# 01-MSP430.net
KiCad netlist of a schematic drawn in Altium Designer
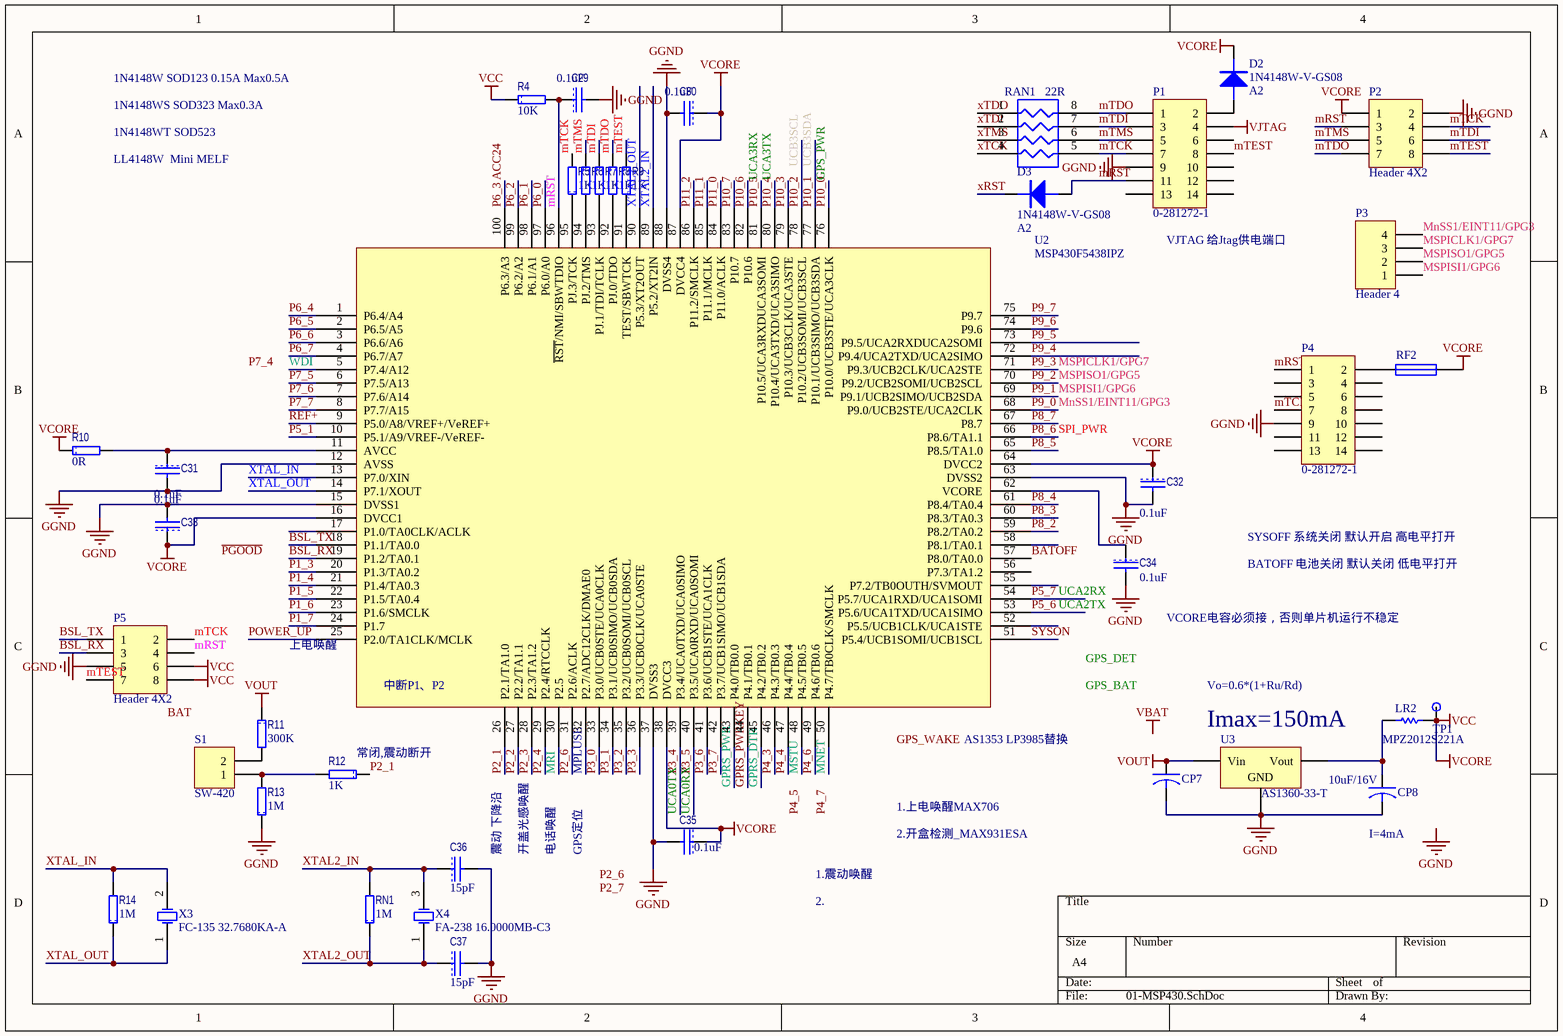
[diagram p0: 01-MSP430.SchDoc]

(export (version "E")
  (design (tool "Eeschema 10.0.6"))
  (components
    (comp (ref "C29")
      (value "0.1uF")
      (footprint "1608[0603]C")
      (description "多层陶瓷电容器MLCC - SMD/SMT 0603 0.1uF 50volts X7R 10%")
      (fields (field (name "MANUFACTURER") "TDK") (field (name "MANUFACTURER PART NUMBER") "C1608X7R1H104K"))
      (libsource (lib "*") (part "CAP"))
    )
    (comp (ref "C30")
      (value "0.1uF")
      (footprint "1608[0603]C")
      (description "多层陶瓷电容器MLCC - SMD/SMT 0603 0.1uF 50volts X7R 10%")
      (fields (field (name "MANUFACTURER") "TDK") (field (name "MANUFACTURER PART NUMBER") "C1608X7R1H104K"))
      (libsource (lib "*") (part "CAP"))
    )
    (comp (ref "C31")
      (value "0.1uF")
      (footprint "1608[0603]C")
      (description "多层陶瓷电容器MLCC - SMD/SMT 0603 0.1uF 50volts X7R 10%")
      (fields (field (name "MANUFACTURER") "TDK") (field (name "MANUFACTURER PART NUMBER") "C1608X7R1H104K"))
      (libsource (lib "*") (part "CAP"))
    )
    (comp (ref "C32")
      (value "0.1uF")
      (footprint "1608[0603]C")
      (description "多层陶瓷电容器MLCC - SMD/SMT 0603 0.1uF 50volts X7R 10%")
      (fields (field (name "MANUFACTURER") "TDK") (field (name "MANUFACTURER PART NUMBER") "C1608X7R1H104K"))
      (libsource (lib "*") (part "CAP"))
    )
    (comp (ref "C33")
      (value "0.1uF")
      (footprint "1608[0603]C")
      (description "多层陶瓷电容器MLCC - SMD/SMT 0603 0.1uF 50volts X7R 10%")
      (fields (field (name "MANUFACTURER") "TDK") (field (name "MANUFACTURER PART NUMBER") "C1608X7R1H104K"))
      (libsource (lib "*") (part "CAP"))
    )
    (comp (ref "C34")
      (value "0.1uF")
      (footprint "1608[0603]C")
      (description "多层陶瓷电容器MLCC - SMD/SMT 0603 0.1uF 50volts X7R 10%")
      (fields (field (name "MANUFACTURER") "TDK") (field (name "MANUFACTURER PART NUMBER") "C1608X7R1H104K"))
      (libsource (lib "*") (part "CAP"))
    )
    (comp (ref "C35")
      (value "0.1uF")
      (footprint "1608[0603]C")
      (description "多层陶瓷电容器MLCC - SMD/SMT 0603 0.1uF 50volts X7R 10%")
      (fields (field (name "MANUFACTURER") "TDK") (field (name "MANUFACTURER PART NUMBER") "C1608X7R1H104K"))
      (libsource (lib "*") (part "CAP"))
    )
    (comp (ref "C36")
      (value "15pF")
      (footprint "1608[0603]")
      (description "多层陶瓷电容器MLCC - SMD/SMT 0603 15pF 50volts C0G 5%")
      (fields (field (name "MANUFACTURER") "TDK") (field (name "MANUFACTURER PART NUMBER") "C1608C0G1H150J"))
      (libsource (lib "*") (part "CAP"))
    )
    (comp (ref "C37")
      (value "15pF")
      (footprint "1608[0603]")
      (description "多层陶瓷电容器MLCC - SMD/SMT 0603 15pF 50volts C0G 5%")
      (fields (field (name "MANUFACTURER") "TDK") (field (name "MANUFACTURER PART NUMBER") "C1608C0G1H150J"))
      (libsource (lib "*") (part "CAP"))
    )
    (comp (ref "CP7")
      (value "TAJA106K016RNJ")
      (footprint "3216[1206]CB")
      (description "钽质电容器-固体SMD 16volts 10uF 10%")
      (fields (field (name "MANUFACTURER") "AVX"))
      (libsource (lib "*") (part "CAPACITOR"))
    )
    (comp (ref "CP8")
      (value "10uF/16V")
      (footprint "3216[1206]CB")
      (description "钽质电容器-固体SMD 16volts 10uF 10%")
      (fields (field (name "MANUFACTURER") "AVX") (field (name "MANUFACTURER PART NUMBER") "TAJA106K016RNJ"))
      (libsource (lib "*") (part "CAPACITOR"))
    )
    (comp (ref "D2")
      (value "1N4148W-V-GS08")
      (footprint "SOD123")
      (description "二极管 - 通用，功率，开关 100V Io/150mA")
      (fields (field (name "MANUFACTURER") "Vishay Semiconductors") (field (name "ALTIUM_VALUE") "A2"))
      (libsource (lib "IN4148") (part "1N4148W"))
    )
    (comp (ref "D3")
      (value "1N4148W-V-GS08")
      (footprint "SOD123")
      (description "二极管 - 通用，功率，开关 100V Io/150mA")
      (fields (field (name "MANUFACTURER") "Vishay Semiconductors") (field (name "ALTIUM_VALUE") "A2"))
      (libsource (lib "IN4148") (part "1N4148W"))
    )
    (comp (ref "LR2")
      (value "MPZ2012S221A")
      (footprint "2012[0805]")
      (description "电磁干扰滤波珠子、扼流圈和阵列 Ferrite Chip Beads")
      (fields (field (name "MANUFACTURER") "TDK"))
      (libsource (lib "Miscellaneous Devices") (part "Res Semi"))
    )
    (comp (ref "P1")
      (value "0-281272-1")
      (footprint "HDR2X7")
      (description "TE CONNECTIVITY 2.54mm / AMP - 0-281272-1 - HEADER STRAIGHT 14WAY")
      (fields (field (name "MANUFACTURER") "TE CONNECTIVITY / AMP"))
      (libsource (lib "Miscellaneous Connectors") (part "Header 7X2"))
    )
    (comp (ref "P2")
      (value "Header 4X2")
      (footprint "HDR2X4")
      (description "插针 Header, 4-Pin, Dual row")
      (fields (field (name "PUBLISHER") "Altium Limited"))
      (libsource (lib "Miscellaneous Connectors") (part "Header 4X2"))
    )
    (comp (ref "P3")
      (value "Header 4")
      (footprint "HDR1X4")
      (description "插针 Header, 4-Pin")
      (fields (field (name "PUBLISHER") "Altium Limited"))
      (libsource (lib "Miscellaneous Connectors") (part "Header 4"))
    )
    (comp (ref "P4")
      (value "0-281272-1")
      (footprint "HDR2X7")
      (description "TE CONNECTIVITY 2.54mm / AMP - 0-281272-1 - HEADER STRAIGHT 14WAY")
      (fields (field (name "MANUFACTURER") "TE CONNECTIVITY / AMP"))
      (libsource (lib "Miscellaneous Connectors") (part "Header 7X2"))
    )
    (comp (ref "P5")
      (value "Header 4X2")
      (footprint "HDR2X4")
      (description "插针 Header, 4-Pin, Dual row")
      (fields (field (name "PUBLISHER") "Altium Limited"))
      (libsource (lib "Miscellaneous Connectors") (part "Header 4X2"))
    )
    (comp (ref "R4")
      (value "10K")
      (footprint "1608[0603]R")
      (description "厚膜电阻器 - SMD 1/10watt 10Kohms 1%")
      (fields
        (field (name "MANUFACTURER") "Vishay / Dale")
        (field (name "MANUFACTURER PART NUMBER") "CRCW060310K0FKEA")
      )
      (libsource (lib "10K 1%") (part "RES"))
    )
    (comp (ref "R5")
      (value "1K")
      (footprint "1608[0603]R")
      (description "厚膜电阻器 - SMD 1/10watt 1.0Kohms 1%")
      (fields
        (field (name "MANUFACTURER") "Vishay / Dale")
        (field (name "MANUFACTURER PART NUMBER") "CRCW06031K00FKEA")
      )
      (libsource (lib "1K 1%") (part "RES"))
    )
    (comp (ref "R6")
      (value "1K")
      (footprint "1608[0603]R")
      (description "厚膜电阻器 - SMD 1/10watt 1.0Kohms 1%")
      (fields
        (field (name "MANUFACTURER") "Vishay / Dale")
        (field (name "MANUFACTURER PART NUMBER") "CRCW06031K00FKEA")
      )
      (libsource (lib "1K 1%") (part "RES"))
    )
    (comp (ref "R7")
      (value "1K")
      (footprint "1608[0603]R")
      (description "厚膜电阻器 - SMD 1/10watt 1.0Kohms 1%")
      (fields
        (field (name "MANUFACTURER") "Vishay / Dale")
        (field (name "MANUFACTURER PART NUMBER") "CRCW06031K00FKEA")
      )
      (libsource (lib "1K 1%") (part "RES"))
    )
    (comp (ref "R8")
      (value "1K")
      (footprint "1608[0603]R")
      (description "厚膜电阻器 - SMD 1/10watt 1.0Kohms 1%")
      (fields
        (field (name "MANUFACTURER") "Vishay / Dale")
        (field (name "MANUFACTURER PART NUMBER") "CRCW06031K00FKEA")
      )
      (libsource (lib "1K 1%") (part "RES"))
    )
    (comp (ref "R9")
      (value "1K")
      (footprint "1608[0603]R")
      (description "厚膜电阻器 - SMD 1/10watt 1.0Kohms 1%")
      (fields
        (field (name "MANUFACTURER") "Vishay / Dale")
        (field (name "MANUFACTURER PART NUMBER") "CRCW06031K00FKEA")
      )
      (libsource (lib "1K 1%") (part "RES"))
    )
    (comp (ref "R10")
      (value "0R")
      (footprint "1608[0603]R")
      (description "厚膜电阻器 - SMD 1/10watt ZEROohm Jumper")
      (fields
        (field (name "MANUFACTURER") "Vishay / Dale")
        (field (name "MANUFACTURER PART NUMBER") "CRCW06030000ZSTA")
      )
      (libsource (lib "0R 1%") (part "RES"))
    )
    (comp (ref "R11")
      (value "300K")
      (footprint "1608[0603]R")
      (description "厚膜电阻器 - SMD 1/10watt 300Kohms 1%")
      (fields
        (field (name "MANUFACTURER") "Vishay / Dale")
        (field (name "MANUFACTURER PART NUMBER") "CRCW0603100KFKEA")
      )
      (libsource (lib "100K 1%") (part "RES"))
    )
    (comp (ref "R12")
      (value "1K")
      (footprint "1608[0603]R")
      (description "厚膜电阻器 - SMD 1/10watt 1.0Kohms 1%")
      (fields
        (field (name "MANUFACTURER") "Vishay / Dale")
        (field (name "MANUFACTURER PART NUMBER") "CRCW06031K00FKEA")
      )
      (libsource (lib "1K 1%") (part "RES"))
    )
    (comp (ref "R13")
      (value "1M")
      (footprint "1608[0603]R")
      (description "厚膜电阻器 - SMD 1/10watt 1.0Mohms 1%")
      (fields
        (field (name "MANUFACTURER") "Vishay / Dale")
        (field (name "MANUFACTURER PART NUMBER") "CRCW06031M00FKEA")
      )
      (libsource (lib "1M 1%") (part "RES"))
    )
    (comp (ref "R14")
      (value "1M")
      (footprint "1608[0603]R")
      (description "厚膜电阻器 - SMD 1/10watt 1.0Mohms 1%")
      (fields
        (field (name "MANUFACTURER") "Vishay / Dale")
        (field (name "MANUFACTURER PART NUMBER") "CRCW06031M00FKEA")
      )
      (libsource (lib "1M 1%") (part "RES"))
    )
    (comp (ref "RAN1")
      (value "22R")
      (footprint "R-AR4")
      (description "电阻器网络与阵列 8Term 22ohms 5% Convex")
      (fields
        (field (name "MANUFACTURER") "Vishay / Dale")
        (field (name "MANUFACTURER PART NUMBER") "CRA06S08322R0JTA")
      )
      (libsource (lib "*") (part "RP4R"))
    )
    (comp (ref "RF2")
      (value "0805L050WR")
      (footprint "2012[0805]F")
      (description "可复位保险丝 PTC 30V POLY SURF MOUNT 0805 .500A")
      (fields (field (name "MANUFACTURER") "Littelfuse"))
      (libsource (lib "*") (part "FUSE1"))
    )
    (comp (ref "RN1")
      (value "1M")
      (footprint "1608[0603]RN")
      (description "厚膜电阻器 - SMD 1/10watt 1.0Mohms 1%")
      (fields
        (field (name "MANUFACTURER") "Vishay / Dale")
        (field (name "MANUFACTURER PART NUMBER") "CRCW06031M00FKEA")
      )
      (libsource (lib "1M 1%") (part "RES"))
    )
    (comp (ref "S1")
      (value "SW-420")
      (footprint "SW-420")
      (description "插针 工业级震动传感器")
      (fields (field (name "PUBLISHER") "Altium Limited"))
      (libsource (lib "Miscellaneous Connectors") (part "Header 2"))
    )
    (comp (ref "TP1")
      (value "TP")
      (footprint "TP")
      (description "Test Point")
      (libsource (lib "S3C2440V9") (part "Test Point"))
    )
    (comp (ref "U2")
      (value "MSP430F5438IPZ")
      (footprint "TQFP100_N")
      (description "IC MCU 16BIT 256K FLASH 100-LQFP")
      (fields
        (field (name "MANUFACTURER") "Texas Instruments")
        (field (name "MANUFACTURER PART NUMBER") "MSP430F5438IPZR")
      )
      (libsource (lib "MSP430") (part "MSP430F5438"))
    )
    (comp (ref "U3")
      (value "AS1360-33-T")
      (footprint "SOT23_N")
      (description "LDO Voltage Controllers")
      (fields (field (name "MANUFACTURER") "ams"))
      (libsource (lib "Miscellaneous Devices") (part "Volt Reg"))
    )
    (comp (ref "X3")
      (value "FC-135 32.7680KA-A")
      (footprint "FC-135")
      (description "晶体 32.768KHz 20ppm 12.5pF -40C -85C")
      (fields (field (name "MANUFACTURER") "Epson Toyocom"))
      (libsource (lib "Miscellaneous Devices") (part "XTAL"))
    )
    (comp (ref "X4")
      (value "FA-238 16.0000MB-C3")
      (footprint "FA-238")
      (description "CRYSTAL 16MHZ 18PF SMD")
      (fields (field (name "MANUFACTURER") "EPSON"))
      (libsource (lib "") (part "XTAL_1"))
    )
  )
  (nets
    (net (code "1") (name "/ACC24") (class "Default")
      (node (ref "U2") (pin "100") (pinfunction "P6.3/A3_100") (pintype "passive"))
    )
    (net (code "3") (name "/BATOFF") (class "Default")
      (node (ref "U2") (pin "57") (pinfunction "P8.0/TA0.0_57") (pintype "passive"))
    )
    (net (code "4") (name "/BSL_RX") (class "Default")
      (node (ref "P5") (pin "3") (pinfunction "3_3") (pintype "passive"))
      (node (ref "U2") (pin "19") (pinfunction "P1.2/TA0.1_19") (pintype "passive"))
    )
    (net (code "5") (name "/BSL_TX") (class "Default")
      (node (ref "P5") (pin "1") (pinfunction "1_1") (pintype "passive"))
      (node (ref "U2") (pin "18") (pinfunction "P1.1/TA0.0_18") (pintype "passive"))
    )
    (net (code "6") (name "/GPRS_DTR") (class "Default")
      (node (ref "U2") (pin "45") (pinfunction "P4.2/TB0.2_45") (pintype "passive"))
    )
    (net (code "7") (name "/GPRS_PWR") (class "Default")
      (node (ref "U2") (pin "43") (pinfunction "P4.0/TB0.0_43") (pintype "passive"))
    )
    (net (code "8") (name "/GPRS_PWRKEY") (class "Default")
      (node (ref "U2") (pin "44") (pinfunction "P4.1/TB0.1_44") (pintype "passive"))
    )
    (net (code "11") (name "/GPS_PWR") (class "Default")
      (node (ref "U2") (pin "76") (pinfunction "P10.0/UCB3STE/UCA3CLK_76") (pintype "passive"))
    )
    (net (code "13") (name "/MNET") (class "Default")
      (node (ref "U2") (pin "50") (pinfunction "P4.7/TB0CLK/SMCLK_50") (pintype "passive"))
    )
    (net (code "14") (name "/MPLUSE") (class "Default")
      (node (ref "U2") (pin "32") (pinfunction "P2.7/ADC12CLK/DMAE0_32") (pintype "passive"))
    )
    (net (code "15") (name "/MRI") (class "Default")
      (node (ref "U2") (pin "30") (pinfunction "P2.5_30") (pintype "passive"))
    )
    (net (code "16") (name "/MSPICLK1{slash}GPG7") (class "Default")
      (node (ref "P3") (pin "3") (pinfunction "3_3") (pintype "passive"))
      (node (ref "U2") (pin "71") (pinfunction "P9.3/UCB2CLK/UCA2STE_71") (pintype "passive"))
    )
    (net (code "17") (name "/MSPISI1{slash}GPG6") (class "Default")
      (node (ref "P3") (pin "1") (pinfunction "1_1") (pintype "passive"))
      (node (ref "U2") (pin "69") (pinfunction "P9.1/UCB2SIMO/UCB2SDA_69") (pintype "passive"))
    )
    (net (code "18") (name "/MSPISO1{slash}GPG5") (class "Default")
      (node (ref "P3") (pin "2") (pinfunction "2_2") (pintype "passive"))
      (node (ref "U2") (pin "70") (pinfunction "P9.2/UCB2SOMI/UCB2SCL_70") (pintype "passive"))
    )
    (net (code "19") (name "/MSTU") (class "Default")
      (node (ref "U2") (pin "48") (pinfunction "P4.5/TB0.5_48") (pintype "passive"))
    )
    (net (code "20") (name "/MnSS1{slash}EINT11{slash}GPG3") (class "Default")
      (node (ref "P3") (pin "4") (pinfunction "4_4") (pintype "passive"))
      (node (ref "U2") (pin "68") (pinfunction "P9.0/UCB2STE/UCA2CLK_68") (pintype "passive"))
    )
    (net (code "21") (name "/P1_3") (class "Default")
      (node (ref "U2") (pin "20") (pinfunction "P1.3/TA0.2_20") (pintype "passive"))
    )
    (net (code "22") (name "/P1_4") (class "Default")
      (node (ref "U2") (pin "21") (pinfunction "P1.4/TA0.3_21") (pintype "passive"))
    )
    (net (code "23") (name "/P1_5") (class "Default")
      (node (ref "U2") (pin "22") (pinfunction "P1.5/TA0.4_22") (pintype "passive"))
    )
    (net (code "24") (name "/P1_6") (class "Default")
      (node (ref "U2") (pin "23") (pinfunction "P1.6/SMCLK_23") (pintype "passive"))
    )
    (net (code "25") (name "/P1_7") (class "Default")
      (node (ref "U2") (pin "24") (pinfunction "P1.7_24") (pintype "passive"))
    )
    (net (code "26") (name "/P2_1") (class "Default")
      (node (ref "R12") (pin "1") (pinfunction "1_1") (pintype "passive"))
      (node (ref "U2") (pin "26") (pinfunction "P2.1/TA1.0_26") (pintype "passive"))
    )
    (net (code "27") (name "/P2_2") (class "Default")
      (node (ref "U2") (pin "27") (pinfunction "P2.2/TA1.1_27") (pintype "passive"))
    )
    (net (code "28") (name "/P2_3") (class "Default")
      (node (ref "U2") (pin "28") (pinfunction "P2.3/TA1.2_28") (pintype "passive"))
    )
    (net (code "29") (name "/P2_4") (class "Default")
      (node (ref "U2") (pin "29") (pinfunction "P2.4/RTCCLK_29") (pintype "passive"))
    )
    (net (code "30") (name "/P2_6") (class "Default")
      (node (ref "U2") (pin "31") (pinfunction "P2.6/ACLK_31") (pintype "passive"))
    )
    (net (code "32") (name "/P3_0") (class "Default")
      (node (ref "U2") (pin "33") (pinfunction "P3.0/UCB0STE/UCA0CLK_33") (pintype "passive"))
    )
    (net (code "33") (name "/P3_1") (class "Default")
      (node (ref "U2") (pin "34") (pinfunction "P3.1/UCB0SIMO/UCB0SDA_34") (pintype "passive"))
    )
    (net (code "34") (name "/P3_2") (class "Default")
      (node (ref "U2") (pin "35") (pinfunction "P3.2/UCB0SOMI/UCB0SCL_35") (pintype "passive"))
    )
    (net (code "35") (name "/P3_3") (class "Default")
      (node (ref "U2") (pin "36") (pinfunction "P3.3/UCB0CLK/UCA0STE_36") (pintype "passive"))
    )
    (net (code "36") (name "/P3_4") (class "Default")
      (node (ref "U2") (pin "39") (pinfunction "P3.4/UCA0TXD/UCA0SIMO_39") (pintype "passive"))
    )
    (net (code "37") (name "/P3_5") (class "Default")
      (node (ref "U2") (pin "40") (pinfunction "P3.5/UCA0RXD/UCA0SOMI_40") (pintype "passive"))
    )
    (net (code "38") (name "/P3_6") (class "Default")
      (node (ref "U2") (pin "41") (pinfunction "P3.6/UCB1STE/UCA1CLK_41") (pintype "passive"))
    )
    (net (code "39") (name "/P3_7") (class "Default")
      (node (ref "U2") (pin "42") (pinfunction "P3.7/UCB1SIMO/UCB1SDA_42") (pintype "passive"))
    )
    (net (code "40") (name "/P4_3") (class "Default")
      (node (ref "U2") (pin "46") (pinfunction "P4.3/TB0.3_46") (pintype "passive"))
    )
    (net (code "41") (name "/P4_4") (class "Default")
      (node (ref "U2") (pin "47") (pinfunction "P4.4/TB0.4_47") (pintype "passive"))
    )
    (net (code "43") (name "/P4_6") (class "Default")
      (node (ref "U2") (pin "49") (pinfunction "P4.6/TB0.6_49") (pintype "passive"))
    )
    (net (code "45") (name "/P5_1") (class "Default")
      (node (ref "U2") (pin "10") (pinfunction "P5.1/A9/VREF-/VeREF-_10") (pintype "passive"))
    )
    (net (code "46") (name "/P5_6") (class "Default")
      (node (ref "U2") (pin "53") (pinfunction "P5.6/UCA1TXD/UCA1SIMO_53") (pintype "passive"))
    )
    (net (code "47") (name "/P5_7") (class "Default")
      (node (ref "U2") (pin "54") (pinfunction "P5.7/UCA1RXD/UCA1SOMI_54") (pintype "passive"))
    )
    (net (code "48") (name "/P6_0") (class "Default")
      (node (ref "U2") (pin "97") (pinfunction "P6.0/A0_97") (pintype "passive"))
    )
    (net (code "49") (name "/P6_1") (class "Default")
      (node (ref "U2") (pin "98") (pinfunction "P6.1/A1_98") (pintype "passive"))
    )
    (net (code "50") (name "/P6_2") (class "Default")
      (node (ref "U2") (pin "99") (pinfunction "P6.2/A2_99") (pintype "passive"))
    )
    (net (code "51") (name "/P6_4") (class "Default")
      (node (ref "U2") (pin "1") (pinfunction "P6.4/A4_1") (pintype "passive"))
    )
    (net (code "52") (name "/P6_5") (class "Default")
      (node (ref "U2") (pin "2") (pinfunction "P6.5/A5_2") (pintype "passive"))
    )
    (net (code "53") (name "/P6_6") (class "Default")
      (node (ref "U2") (pin "3") (pinfunction "P6.6/A6_3") (pintype "passive"))
    )
    (net (code "54") (name "/P6_7") (class "Default")
      (node (ref "U2") (pin "4") (pinfunction "P6.7/A7_4") (pintype "passive"))
    )
    (net (code "56") (name "/P7_5") (class "Default")
      (node (ref "U2") (pin "6") (pinfunction "P7.5/A13_6") (pintype "passive"))
    )
    (net (code "57") (name "/P7_6") (class "Default")
      (node (ref "U2") (pin "7") (pinfunction "P7.6/A14_7") (pintype "passive"))
    )
    (net (code "58") (name "/P7_7") (class "Default")
      (node (ref "U2") (pin "8") (pinfunction "P7.7/A15_8") (pintype "passive"))
    )
    (net (code "59") (name "/P8_2") (class "Default")
      (node (ref "U2") (pin "59") (pinfunction "P8.2/TA0.2_59") (pintype "passive"))
    )
    (net (code "60") (name "/P8_3") (class "Default")
      (node (ref "U2") (pin "60") (pinfunction "P8.3/TA0.3_60") (pintype "passive"))
    )
    (net (code "61") (name "/P8_4") (class "Default")
      (node (ref "U2") (pin "61") (pinfunction "P8.4/TA0.4_61") (pintype "passive"))
    )
    (net (code "62") (name "/P8_5") (class "Default")
      (node (ref "U2") (pin "65") (pinfunction "P8.5/TA1.0_65") (pintype "passive"))
    )
    (net (code "63") (name "/P8_6") (class "Default")
      (node (ref "U2") (pin "66") (pinfunction "P8.6/TA1.1_66") (pintype "passive"))
    )
    (net (code "64") (name "/P8_7") (class "Default")
      (node (ref "U2") (pin "67") (pinfunction "P8.7_67") (pintype "passive"))
    )
    (net (code "65") (name "/P9_4") (class "Default")
      (node (ref "U2") (pin "72") (pinfunction "P9.4/UCA2TXD/UCA2SIMO_72") (pintype "passive"))
    )
    (net (code "66") (name "/P9_5") (class "Default")
      (node (ref "U2") (pin "73") (pinfunction "P9.5/UCA2RXDUCA2SOMI_73") (pintype "passive"))
    )
    (net (code "67") (name "/P9_6") (class "Default")
      (node (ref "U2") (pin "74") (pinfunction "P9.6_74") (pintype "passive"))
    )
    (net (code "68") (name "/P9_7") (class "Default")
      (node (ref "U2") (pin "75") (pinfunction "P9.7_75") (pintype "passive"))
    )
    (net (code "69") (name "/P10_1") (class "Default")
      (node (ref "U2") (pin "77") (pinfunction "P10.1/UCB3SIMO/UCB3SDA_77") (pintype "passive"))
    )
    (net (code "70") (name "/P10_2") (class "Default")
      (node (ref "U2") (pin "78") (pinfunction "P10.2/UCB3SOMI/UCB3SCL_78") (pintype "passive"))
    )
    (net (code "71") (name "/P10_3") (class "Default")
      (node (ref "U2") (pin "79") (pinfunction "P10.3/UCB3CLK/UCA3STE_79") (pintype "passive"))
    )
    (net (code "72") (name "/P10_4") (class "Default")
      (node (ref "U2") (pin "80") (pinfunction "P10.4/UCA3TXD/UCA3SIMO_80") (pintype "passive"))
    )
    (net (code "73") (name "/P10_5") (class "Default")
      (node (ref "U2") (pin "81") (pinfunction "P10.5/UCA3RXDUCA3SOMI_81") (pintype "passive"))
    )
    (net (code "74") (name "/P10_6") (class "Default")
      (node (ref "U2") (pin "82") (pinfunction "P10.6_82") (pintype "passive"))
    )
    (net (code "75") (name "/P10_7") (class "Default")
      (node (ref "U2") (pin "83") (pinfunction "P10.7_83") (pintype "passive"))
    )
    (net (code "76") (name "/P11_0") (class "Default")
      (node (ref "U2") (pin "84") (pinfunction "P11.0/ACLK_84") (pintype "passive"))
    )
    (net (code "77") (name "/P11_1") (class "Default")
      (node (ref "U2") (pin "85") (pinfunction "P11.1/MCLK_85") (pintype "passive"))
    )
    (net (code "78") (name "/P11_2") (class "Default")
      (node (ref "U2") (pin "86") (pinfunction "P11.2/SMCLK_86") (pintype "passive"))
    )
    (net (code "79") (name "/POWER_UP") (class "Default")
      (node (ref "U2") (pin "25") (pinfunction "P2.0/TA1CLK/MCLK_25") (pintype "passive"))
    )
    (net (code "80") (name "/REF+") (class "Default")
      (node (ref "U2") (pin "9") (pinfunction "P5.0/A8/VREF+/VeREF+_9") (pintype "passive"))
    )
    (net (code "81") (name "/SYSON") (class "Default")
      (node (ref "U2") (pin "51") (pinfunction "P5.4/UCB1SOMI/UCB1SCL_51") (pintype "passive"))
    )
    (net (code "82") (name "/WDI") (class "Default")
      (node (ref "U2") (pin "5") (pinfunction "P7.4/A12_5") (pintype "passive"))
    )
    (net (code "83") (name "/XTAL2_IN") (class "Default")
      (node (ref "C36") (pin "1") (pinfunction "1_1") (pintype "passive"))
      (node (ref "RN1") (pin "2") (pinfunction "2_2") (pintype "passive"))
      (node (ref "U2") (pin "89") (pinfunction "P5.2/XT2IN_89") (pintype "passive"))
      (node (ref "X4") (pin "3") (pinfunction "OSC2_3") (pintype "passive"))
    )
    (net (code "84") (name "/XTAL2_OUT") (class "Default")
      (node (ref "C37") (pin "1") (pinfunction "1_1") (pintype "passive"))
      (node (ref "RN1") (pin "1") (pinfunction "1_1") (pintype "passive"))
      (node (ref "U2") (pin "90") (pinfunction "P5.3/XT2OUT_90") (pintype "passive"))
      (node (ref "X4") (pin "1") (pinfunction "OSC1_1") (pintype "passive"))
    )
    (net (code "85") (name "/XTAL_IN") (class "Default")
      (node (ref "R14") (pin "2") (pinfunction "2_2") (pintype "passive"))
      (node (ref "U2") (pin "13") (pinfunction "P7.0/XIN_13") (pintype "passive"))
      (node (ref "X3") (pin "2") (pinfunction "OSC2_2") (pintype "passive"))
    )
    (net (code "86") (name "/XTAL_OUT") (class "Default")
      (node (ref "R14") (pin "1") (pinfunction "1_1") (pintype "passive"))
      (node (ref "U2") (pin "14") (pinfunction "P7.1/XOUT_14") (pintype "passive"))
      (node (ref "X3") (pin "1") (pinfunction "OSC1_1") (pintype "passive"))
    )
    (net (code "87") (name "/mRST") (class "Default")
      (node (ref "C29") (pin "1") (pinfunction "1_1") (pintype "passive"))
      (node (ref "D3") (pin "1") (pinfunction "A_1") (pintype "passive"))
      (node (ref "P1") (pin "11") (pinfunction "11_11") (pintype "passive"))
      (node (ref "P2") (pin "3") (pinfunction "3_3") (pintype "passive"))
      (node (ref "P4") (pin "1") (pinfunction "1_1") (pintype "passive"))
      (node (ref "P5") (pin "4") (pinfunction "4_4") (pintype "passive"))
      (node (ref "R4") (pin "2") (pinfunction "2_2") (pintype "passive"))
      (node (ref "U2") (pin "96") (pinfunction "~{RST}/NMI/SBWTDIO_96") (pintype "passive"))
    )
    (net (code "88") (name "/mTCK") (class "Default")
      (node (ref "P1") (pin "7") (pinfunction "7_7") (pintype "passive"))
      (node (ref "P2") (pin "4") (pinfunction "4_4") (pintype "passive"))
      (node (ref "P4") (pin "7") (pinfunction "7_7") (pintype "passive"))
      (node (ref "P5") (pin "2") (pinfunction "2_2") (pintype "passive"))
      (node (ref "R5") (pin "2") (pinfunction "2_2") (pintype "passive"))
      (node (ref "RAN1") (pin "5") (pinfunction "R4_5") (pintype "passive"))
    )
    (net (code "89") (name "/mTDI") (class "Default")
      (node (ref "P1") (pin "3") (pinfunction "3_3") (pintype "passive"))
      (node (ref "P2") (pin "6") (pinfunction "6_6") (pintype "passive"))
      (node (ref "R7") (pin "1") (pinfunction "1_1") (pintype "passive"))
      (node (ref "RAN1") (pin "7") (pinfunction "R2_7") (pintype "passive"))
    )
    (net (code "90") (name "/mTDO") (class "Default")
      (node (ref "P1") (pin "1") (pinfunction "1_1") (pintype "passive"))
      (node (ref "P2") (pin "7") (pinfunction "7_7") (pintype "passive"))
      (node (ref "R8") (pin "1") (pinfunction "1_1") (pintype "passive"))
      (node (ref "RAN1") (pin "8") (pinfunction "R1_8") (pintype "passive"))
    )
    (net (code "91") (name "/mTEST") (class "Default")
      (node (ref "P1") (pin "8") (pinfunction "8_8") (pintype "passive"))
      (node (ref "P2") (pin "8") (pinfunction "8_8") (pintype "passive"))
      (node (ref "P5") (pin "7") (pinfunction "7_7") (pintype "passive"))
      (node (ref "R9") (pin "1") (pinfunction "1_1") (pintype "passive"))
    )
    (net (code "92") (name "/mTMS") (class "Default")
      (node (ref "P1") (pin "5") (pinfunction "5_5") (pintype "passive"))
      (node (ref "P2") (pin "5") (pinfunction "5_5") (pintype "passive"))
      (node (ref "R6") (pin "1") (pinfunction "1_1") (pintype "passive"))
      (node (ref "RAN1") (pin "6") (pinfunction "R3_6") (pintype "passive"))
    )
    (net (code "93") (name "/xRST") (class "Default")
      (node (ref "D3") (pin "2") (pinfunction "K_2") (pintype "passive"))
    )
    (net (code "94") (name "/xTCK") (class "Default")
      (node (ref "RAN1") (pin "4") (pinfunction "R4_4") (pintype "passive"))
    )
    (net (code "95") (name "/xTDI") (class "Default")
      (node (ref "RAN1") (pin "2") (pinfunction "R2_2") (pintype "passive"))
    )
    (net (code "96") (name "/xTDO") (class "Default")
      (node (ref "RAN1") (pin "1") (pinfunction "R1_1") (pintype "passive"))
    )
    (net (code "97") (name "/xTMS") (class "Default")
      (node (ref "RAN1") (pin "3") (pinfunction "R3_3") (pintype "passive"))
    )
    (net (code "99") (name "GGND") (class "Default")
      (node (ref "C29") (pin "2") (pinfunction "2_2") (pintype "passive"))
      (node (ref "C30") (pin "2") (pinfunction "2_2") (pintype "passive"))
      (node (ref "C31") (pin "2") (pinfunction "2_2") (pintype "passive"))
      (node (ref "C32") (pin "2") (pinfunction "2_2") (pintype "passive"))
      (node (ref "C33") (pin "2") (pinfunction "2_2") (pintype "passive"))
      (node (ref "C34") (pin "2") (pinfunction "2_2") (pintype "passive"))
      (node (ref "C35") (pin "2") (pinfunction "2_2") (pintype "passive"))
      (node (ref "C36") (pin "2") (pinfunction "2_2") (pintype "passive"))
      (node (ref "C37") (pin "2") (pinfunction "2_2") (pintype "passive"))
      (node (ref "CP7") (pin "2") (pinfunction "2_2") (pintype "passive"))
      (node (ref "CP8") (pin "2") (pinfunction "2_2") (pintype "passive"))
      (node (ref "P1") (pin "9") (pinfunction "9_9") (pintype "passive"))
      (node (ref "P2") (pin "2") (pinfunction "2_2") (pintype "passive"))
      (node (ref "P4") (pin "9") (pinfunction "9_9") (pintype "passive"))
      (node (ref "P5") (pin "5") (pinfunction "5_5") (pintype "passive"))
      (node (ref "R13") (pin "1") (pinfunction "1_1") (pintype "passive"))
      (node (ref "U2") (pin "12") (pinfunction "AVSS_12") (pintype "passive"))
      (node (ref "U2") (pin "15") (pinfunction "DVSS1_15") (pintype "passive"))
      (node (ref "U2") (pin "37") (pinfunction "DVSS3_37") (pintype "passive"))
      (node (ref "U2") (pin "63") (pinfunction "DVSS2_63") (pintype "passive"))
      (node (ref "U2") (pin "88") (pinfunction "DVSS4_88") (pintype "passive"))
      (node (ref "U3") (pin "1") (pinfunction "GND_1") (pintype "passive"))
    )
    (net (code "100") (name "Net-(D2-A)") (class "Default")
      (node (ref "D2") (pin "1") (pinfunction "A_1") (pintype "passive"))
      (node (ref "P1") (pin "2") (pinfunction "2_2") (pintype "passive"))
    )
    (net (code "101") (name "Net-(R11-Pad2)") (class "Default")
      (node (ref "R11") (pin "2") (pinfunction "2_2") (pintype "passive"))
      (node (ref "S1") (pin "2") (pinfunction "2_2") (pintype "passive"))
    )
    (net (code "102") (name "Net-(R12-Pad2)") (class "Default")
      (node (ref "R12") (pin "2") (pinfunction "2_2") (pintype "passive"))
      (node (ref "R13") (pin "2") (pinfunction "2_2") (pintype "passive"))
      (node (ref "S1") (pin "1") (pinfunction "1_1") (pintype "passive"))
    )
    (net (code "103") (name "Net-(U2-AVCC)") (class "Default")
      (node (ref "C31") (pin "1") (pinfunction "1_1") (pintype "passive"))
      (node (ref "R10") (pin "2") (pinfunction "2_2") (pintype "passive"))
      (node (ref "U2") (pin "11") (pinfunction "AVCC_11") (pintype "passive"))
    )
    (net (code "104") (name "Net-(U2-PJ.0{slash}TDO)") (class "Default")
      (node (ref "R8") (pin "2") (pinfunction "2_2") (pintype "passive"))
      (node (ref "U2") (pin "92") (pinfunction "PJ.0/TDO_92") (pintype "passive"))
    )
    (net (code "105") (name "Net-(U2-PJ.1{slash}TDI{slash}TCLK)") (class "Default")
      (node (ref "R7") (pin "2") (pinfunction "2_2") (pintype "passive"))
      (node (ref "U2") (pin "93") (pinfunction "PJ.1/TDI/TCLK_93") (pintype "passive"))
    )
    (net (code "106") (name "Net-(U2-PJ.2{slash}TMS)") (class "Default")
      (node (ref "R6") (pin "2") (pinfunction "2_2") (pintype "passive"))
      (node (ref "U2") (pin "94") (pinfunction "PJ.2/TMS_94") (pintype "passive"))
    )
    (net (code "107") (name "Net-(U2-PJ.3{slash}TCK)") (class "Default")
      (node (ref "R5") (pin "1") (pinfunction "1_1") (pintype "passive"))
      (node (ref "U2") (pin "95") (pinfunction "PJ.3/TCK_95") (pintype "passive"))
    )
    (net (code "108") (name "Net-(U2-TEST{slash}SBWTCK)") (class "Default")
      (node (ref "R9") (pin "2") (pinfunction "2_2") (pintype "passive"))
      (node (ref "U2") (pin "91") (pinfunction "TEST/SBWTCK_91") (pintype "passive"))
    )
    (net (code "109") (name "Net-(U2-VCORE)") (class "Default")
      (node (ref "C34") (pin "1") (pinfunction "1_1") (pintype "passive"))
      (node (ref "U2") (pin "62") (pinfunction "VCORE_62") (pintype "passive"))
    )
    (net (code "110") (name "Net-(U3-Vout)") (class "Default")
      (node (ref "CP8") (pin "1") (pinfunction "1_1") (pintype "passive"))
      (node (ref "LR2") (pin "2") (pinfunction "2_2") (pintype "passive"))
      (node (ref "U3") (pin "2") (pinfunction "Vout_2") (pintype "passive"))
    )
    (net (code "112") (name "VCC") (class "Default")
      (node (ref "C30") (pin "1") (pinfunction "1_1") (pintype "passive"))
      (node (ref "C32") (pin "1") (pinfunction "1_1") (pintype "passive"))
      (node (ref "C33") (pin "1") (pinfunction "1_1") (pintype "passive"))
      (node (ref "C35") (pin "1") (pinfunction "1_1") (pintype "passive"))
      (node (ref "D2") (pin "2") (pinfunction "K_2") (pintype "passive"))
      (node (ref "LR2") (pin "1") (pinfunction "1_1") (pintype "passive"))
      (node (ref "P2") (pin "1") (pinfunction "1_1") (pintype "passive"))
      (node (ref "P5") (pin "6") (pinfunction "6_6") (pintype "passive"))
      (node (ref "P5") (pin "8") (pinfunction "8_8") (pintype "passive"))
      (node (ref "R10") (pin "1") (pinfunction "1_1") (pintype "passive"))
      (node (ref "R4") (pin "1") (pinfunction "1_1") (pintype "passive"))
      (node (ref "RF2") (pin "2") (pinfunction "2_2") (pintype "passive"))
      (node (ref "TP1") (pin "1") (pinfunction "TestPoint_1") (pintype "passive"))
      (node (ref "U2") (pin "16") (pinfunction "DVCC1_16") (pintype "passive"))
      (node (ref "U2") (pin "38") (pinfunction "DVCC3_38") (pintype "passive"))
      (node (ref "U2") (pin "64") (pinfunction "DVCC2_64") (pintype "passive"))
      (node (ref "U2") (pin "87") (pinfunction "DVCC4_87") (pintype "passive"))
    )
    (net (code "113") (name "VJTAG") (class "Default")
      (node (ref "P1") (pin "4") (pinfunction "4_4") (pintype "passive"))
    )
    (net (code "114") (name "VOUT") (class "Default")
      (node (ref "CP7") (pin "1") (pinfunction "1_1") (pintype "passive"))
      (node (ref "R11") (pin "1") (pinfunction "1_1") (pintype "passive"))
      (node (ref "U3") (pin "3") (pinfunction "Vin_3") (pintype "passive"))
    )
    (net (code "115") (name "unconnected-(P1-Pad6)") (class "Default")
      (node (ref "P1") (pin "6") (pinfunction "6_6") (pintype "passive"))
    )
    (net (code "116") (name "unconnected-(P1-Pad10)") (class "Default")
      (node (ref "P1") (pin "10") (pinfunction "10_10") (pintype "passive"))
    )
    (net (code "117") (name "unconnected-(P1-Pad12)") (class "Default")
      (node (ref "P1") (pin "12") (pinfunction "12_12") (pintype "passive"))
    )
    (net (code "118") (name "unconnected-(P1-Pad13)") (class "Default")
      (node (ref "P1") (pin "13") (pinfunction "13_13") (pintype "passive"))
    )
    (net (code "119") (name "unconnected-(P1-Pad14)") (class "Default")
      (node (ref "P1") (pin "14") (pinfunction "14_14") (pintype "passive"))
    )
    (net (code "120") (name "unconnected-(P4-Pad2)") (class "Default")
      (node (ref "P4") (pin "2") (pinfunction "2_2") (pintype "passive"))
    )
    (net (code "121") (name "unconnected-(P4-Pad3)") (class "Default")
      (node (ref "P4") (pin "3") (pinfunction "3_3") (pintype "passive"))
    )
    (net (code "122") (name "unconnected-(P4-Pad4)") (class "Default")
      (node (ref "P4") (pin "4") (pinfunction "4_4") (pintype "passive"))
    )
    (net (code "123") (name "unconnected-(P4-Pad5)") (class "Default")
      (node (ref "P4") (pin "5") (pinfunction "5_5") (pintype "passive"))
    )
    (net (code "124") (name "unconnected-(P4-Pad6)") (class "Default")
      (node (ref "P4") (pin "6") (pinfunction "6_6") (pintype "passive"))
    )
    (net (code "125") (name "unconnected-(P4-Pad8)") (class "Default")
      (node (ref "P4") (pin "8") (pinfunction "8_8") (pintype "passive"))
    )
    (net (code "126") (name "unconnected-(P4-Pad10)") (class "Default")
      (node (ref "P4") (pin "10") (pinfunction "10_10") (pintype "passive"))
    )
    (net (code "127") (name "unconnected-(P4-Pad11)") (class "Default")
      (node (ref "P4") (pin "11") (pinfunction "11_11") (pintype "passive"))
    )
    (net (code "128") (name "unconnected-(P4-Pad12)") (class "Default")
      (node (ref "P4") (pin "12") (pinfunction "12_12") (pintype "passive"))
    )
    (net (code "129") (name "unconnected-(P4-Pad13)") (class "Default")
      (node (ref "P4") (pin "13") (pinfunction "13_13") (pintype "passive"))
    )
    (net (code "130") (name "unconnected-(P4-Pad14)") (class "Default")
      (node (ref "P4") (pin "14") (pinfunction "14_14") (pintype "passive"))
    )
    (net (code "131") (name "unconnected-(RF2-Pad1)") (class "Default")
      (node (ref "RF2") (pin "1") (pinfunction "1_1") (pintype "passive"))
    )
    (net (code "132") (name "unconnected-(U2-P1.0{slash}TA0CLK{slash}ACLK-Pad17)") (class "Default")
      (node (ref "U2") (pin "17") (pinfunction "P1.0/TA0CLK/ACLK_17") (pintype "passive"))
    )
    (net (code "133") (name "unconnected-(U2-P5.5{slash}UCB1CLK{slash}UCA1STE-Pad52)") (class "Default")
      (node (ref "U2") (pin "52") (pinfunction "P5.5/UCB1CLK/UCA1STE_52") (pintype "passive"))
    )
    (net (code "134") (name "unconnected-(U2-P7.2{slash}TB0OUTH{slash}SVMOUT-Pad55)") (class "Default")
      (node (ref "U2") (pin "55") (pinfunction "P7.2/TB0OUTH/SVMOUT_55") (pintype "passive"))
    )
    (net (code "135") (name "unconnected-(U2-P7.3{slash}TA1.2-Pad56)") (class "Default")
      (node (ref "U2") (pin "56") (pinfunction "P7.3/TA1.2_56") (pintype "passive"))
    )
    (net (code "136") (name "unconnected-(U2-P8.1{slash}TA0.1-Pad58)") (class "Default")
      (node (ref "U2") (pin "58") (pinfunction "P8.1/TA0.1_58") (pintype "passive"))
    )
  )
)
